# fpga-bank1.net
KiCad netlist of a schematic drawn in Altium Designer
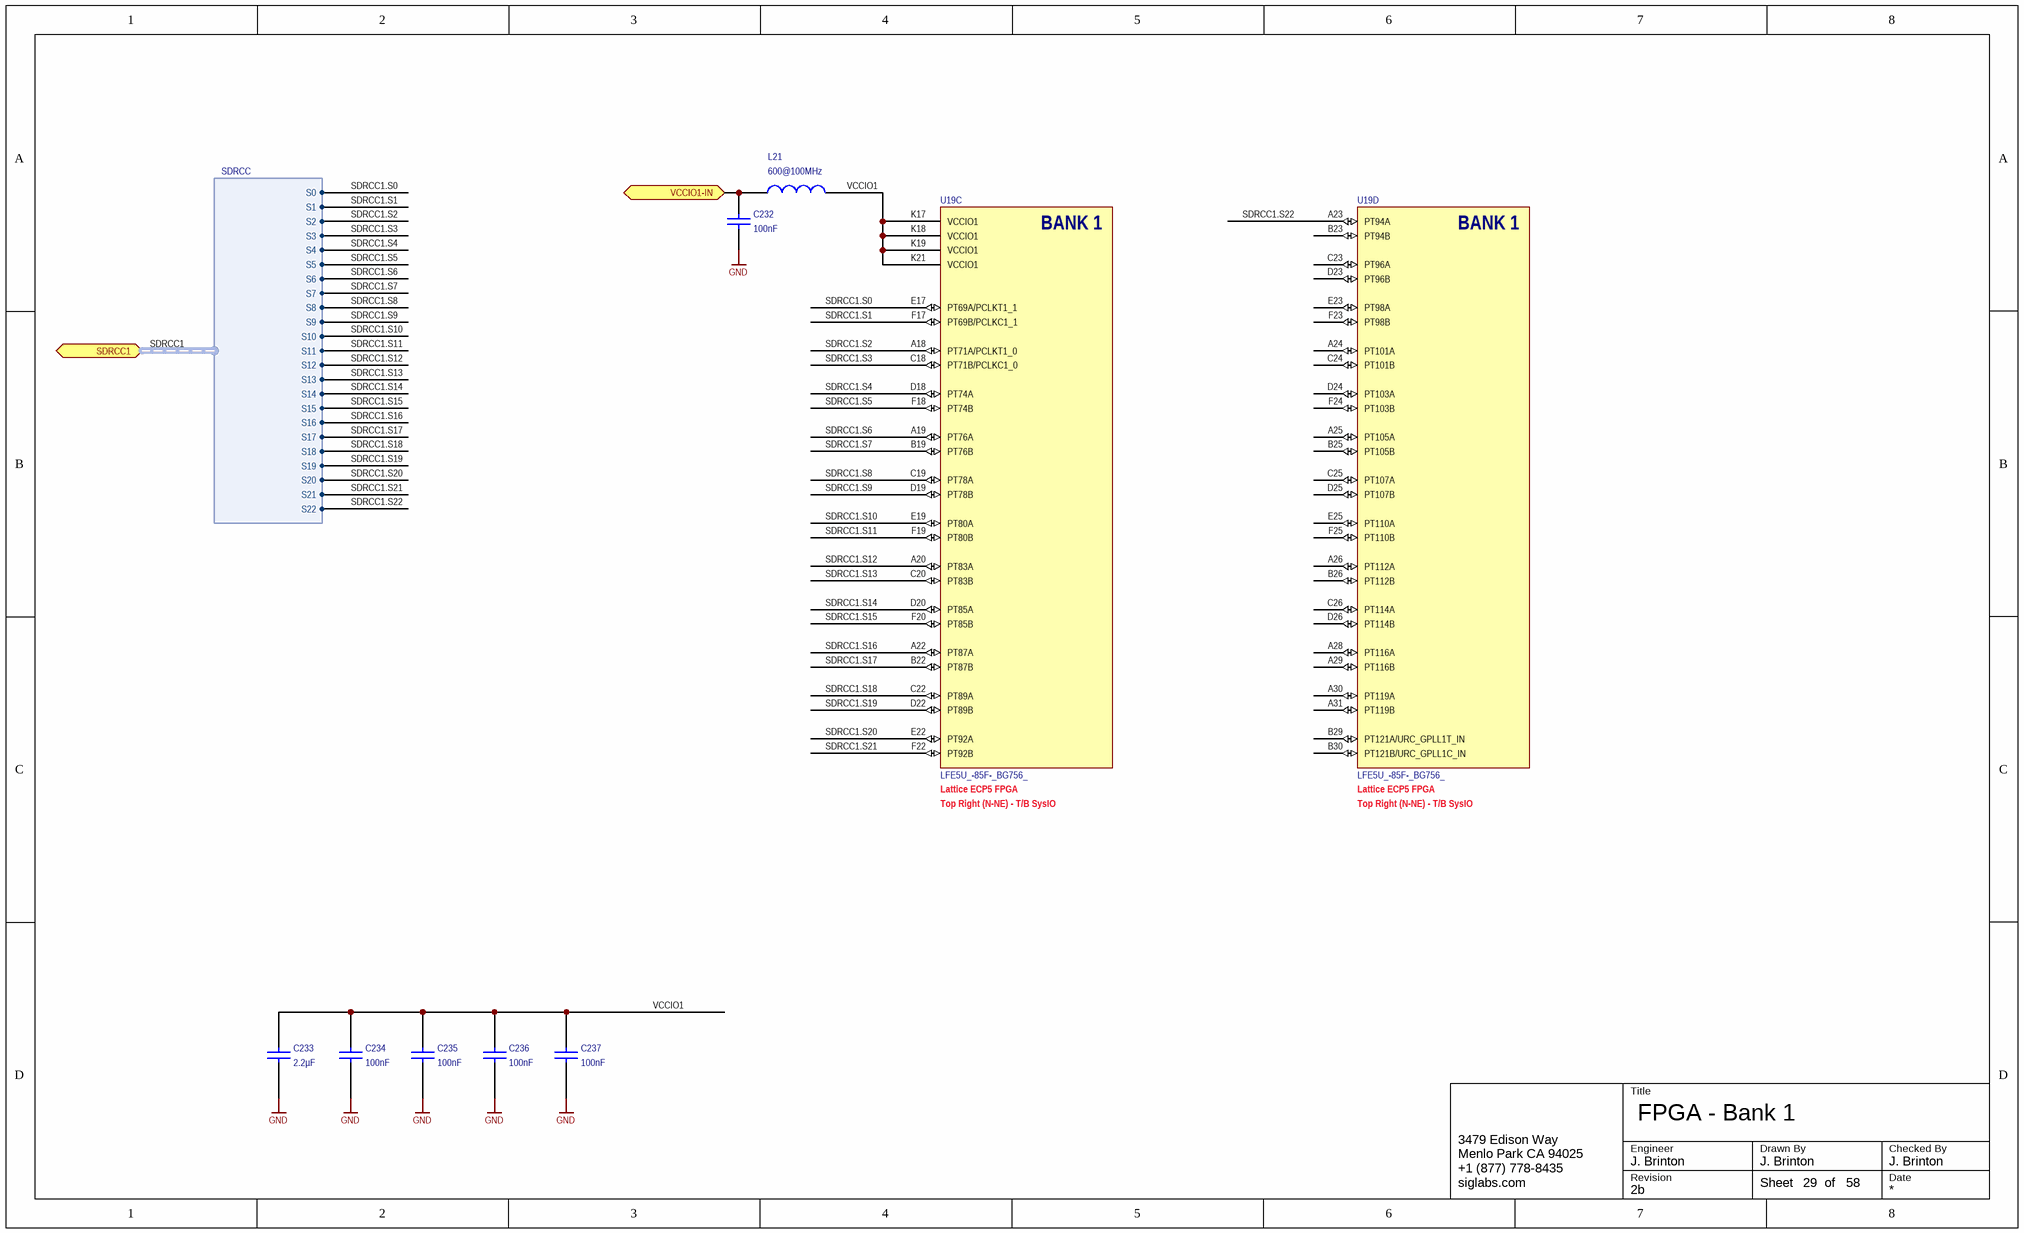
[diagram p0: fpga-bank1.SchDoc]

(export (version "E")
  (design (tool "Eeschema 10.0.6"))
  (components
    (comp (ref "C232")
      (value "100nF")
      (footprint "generic:CAPC1005X56N")
      (description "Ceramic Capacitor 100nF ±10% 16V X7R 0402")
      (fields (field (name "MANUFACTURER") "Murata") (field (name "TOLERANCE") "±10%"))
      (libsource (lib "murata") (part "GRM155R71A104KA01J"))
    )
    (comp (ref "C233")
      (value "2.2µF")
      (footprint "generic:CAPC1608X90N")
      (description "Ceramic Capacitor 2.2uF ±10% 10V X7R 0603")
      (fields (field (name "MANUFACTURER") "Murata") (field (name "TOLERANCE") "±10%"))
      (libsource (lib "murata") (part "GRM188R71A225KE15D"))
    )
    (comp (ref "C234")
      (value "100nF")
      (footprint "generic:CAPC1005X56N")
      (description "Ceramic Capacitor 100nF ±10% 16V X7R 0402")
      (fields (field (name "MANUFACTURER") "Murata") (field (name "TOLERANCE") "±10%"))
      (libsource (lib "murata") (part "GRM155R71A104KA01J"))
    )
    (comp (ref "C235")
      (value "100nF")
      (footprint "generic:CAPC1005X56N")
      (description "Ceramic Capacitor 100nF ±10% 16V X7R 0402")
      (fields (field (name "MANUFACTURER") "Murata") (field (name "TOLERANCE") "±10%"))
      (libsource (lib "murata") (part "GRM155R71A104KA01J"))
    )
    (comp (ref "C236")
      (value "100nF")
      (footprint "generic:CAPC1005X56N")
      (description "Ceramic Capacitor 100nF ±10% 16V X7R 0402")
      (fields (field (name "MANUFACTURER") "Murata") (field (name "TOLERANCE") "±10%"))
      (libsource (lib "murata") (part "GRM155R71A104KA01J"))
    )
    (comp (ref "C237")
      (value "100nF")
      (footprint "generic:CAPC1005X56N")
      (description "Ceramic Capacitor 100nF ±10% 16V X7R 0402")
      (fields (field (name "MANUFACTURER") "Murata") (field (name "TOLERANCE") "±10%"))
      (libsource (lib "murata") (part "GRM155R71A104KA01J"))
    )
    (comp (ref "L21")
      (value "600@100MHz")
      (footprint "0402")
      (description "Ferrite Bead 600-Ohm @ 100MHz 900mA 0402")
      (fields (field (name "MANUFACTURER") "Murata") (field (name "TOLERANCE") "±25%"))
      (libsource (lib "Graviton") (part "IND 0402"))
    )
    (comp (ref "U19")
      (value "LFE5U_-85F-_BG756_")
      (footprint "lattice:caBGA756")
      (description "ECP5 FPGA, 85k LUT, 756-caBGA")
      (fields (field (name "MANUFACTURER") "Lattice Semiconductor"))
      (libsource (lib "lattice") (part "LFE5U_-85F-_BG756_"))
    )
  )
  (nets
    (net (code "2") (name "/SDRCC1.S0") (class "Default")
      (node (ref "U19") (pin "E17") (pinfunction "PT69A/PCLKT1_1_E17") (pintype "bidirectional"))
    )
    (net (code "3") (name "/SDRCC1.S1") (class "Default")
      (node (ref "U19") (pin "F17") (pinfunction "PT69B/PCLKC1_1_F17") (pintype "bidirectional"))
    )
    (net (code "4") (name "/SDRCC1.S2") (class "Default")
      (node (ref "U19") (pin "A18") (pinfunction "PT71A/PCLKT1_0_A18") (pintype "bidirectional"))
    )
    (net (code "5") (name "/SDRCC1.S3") (class "Default")
      (node (ref "U19") (pin "C18") (pinfunction "PT71B/PCLKC1_0_C18") (pintype "bidirectional"))
    )
    (net (code "6") (name "/SDRCC1.S4") (class "Default")
      (node (ref "U19") (pin "D18") (pinfunction "PT74A_D18") (pintype "bidirectional"))
    )
    (net (code "7") (name "/SDRCC1.S5") (class "Default")
      (node (ref "U19") (pin "F18") (pinfunction "PT74B_F18") (pintype "bidirectional"))
    )
    (net (code "8") (name "/SDRCC1.S6") (class "Default")
      (node (ref "U19") (pin "A19") (pinfunction "PT76A_A19") (pintype "bidirectional"))
    )
    (net (code "9") (name "/SDRCC1.S7") (class "Default")
      (node (ref "U19") (pin "B19") (pinfunction "PT76B_B19") (pintype "bidirectional"))
    )
    (net (code "10") (name "/SDRCC1.S8") (class "Default")
      (node (ref "U19") (pin "C19") (pinfunction "PT78A_C19") (pintype "bidirectional"))
    )
    (net (code "11") (name "/SDRCC1.S9") (class "Default")
      (node (ref "U19") (pin "D19") (pinfunction "PT78B_D19") (pintype "bidirectional"))
    )
    (net (code "12") (name "/SDRCC1.S10") (class "Default")
      (node (ref "U19") (pin "E19") (pinfunction "PT80A_E19") (pintype "bidirectional"))
    )
    (net (code "13") (name "/SDRCC1.S11") (class "Default")
      (node (ref "U19") (pin "F19") (pinfunction "PT80B_F19") (pintype "bidirectional"))
    )
    (net (code "14") (name "/SDRCC1.S12") (class "Default")
      (node (ref "U19") (pin "A20") (pinfunction "PT83A_A20") (pintype "bidirectional"))
    )
    (net (code "15") (name "/SDRCC1.S13") (class "Default")
      (node (ref "U19") (pin "C20") (pinfunction "PT83B_C20") (pintype "bidirectional"))
    )
    (net (code "16") (name "/SDRCC1.S14") (class "Default")
      (node (ref "U19") (pin "D20") (pinfunction "PT85A_D20") (pintype "bidirectional"))
    )
    (net (code "17") (name "/SDRCC1.S15") (class "Default")
      (node (ref "U19") (pin "F20") (pinfunction "PT85B_F20") (pintype "bidirectional"))
    )
    (net (code "18") (name "/SDRCC1.S16") (class "Default")
      (node (ref "U19") (pin "A22") (pinfunction "PT87A_A22") (pintype "bidirectional"))
    )
    (net (code "19") (name "/SDRCC1.S17") (class "Default")
      (node (ref "U19") (pin "B22") (pinfunction "PT87B_B22") (pintype "bidirectional"))
    )
    (net (code "20") (name "/SDRCC1.S18") (class "Default")
      (node (ref "U19") (pin "C22") (pinfunction "PT89A_C22") (pintype "bidirectional"))
    )
    (net (code "21") (name "/SDRCC1.S19") (class "Default")
      (node (ref "U19") (pin "D22") (pinfunction "PT89B_D22") (pintype "bidirectional"))
    )
    (net (code "22") (name "/SDRCC1.S20") (class "Default")
      (node (ref "U19") (pin "E22") (pinfunction "PT92A_E22") (pintype "bidirectional"))
    )
    (net (code "23") (name "/SDRCC1.S21") (class "Default")
      (node (ref "U19") (pin "F22") (pinfunction "PT92B_F22") (pintype "bidirectional"))
    )
    (net (code "24") (name "/SDRCC1.S22") (class "Default")
      (node (ref "U19") (pin "A23") (pinfunction "PT94A_A23") (pintype "bidirectional"))
    )
    (net (code "26") (name "/VCCIO1") (class "Default")
      (node (ref "C233") (pin "2") (pinfunction "2_2") (pintype "passive"))
      (node (ref "C234") (pin "2") (pinfunction "2_2") (pintype "passive"))
      (node (ref "C235") (pin "2") (pinfunction "2_2") (pintype "passive"))
      (node (ref "C236") (pin "2") (pinfunction "2_2") (pintype "passive"))
      (node (ref "C237") (pin "2") (pinfunction "2_2") (pintype "passive"))
      (node (ref "L21") (pin "1") (pinfunction "1_1") (pintype "passive"))
      (node (ref "U19") (pin "K17") (pinfunction "VCCIO1_K17") (pintype "power_in"))
      (node (ref "U19") (pin "K18") (pinfunction "VCCIO1_K18") (pintype "power_in"))
      (node (ref "U19") (pin "K19") (pinfunction "VCCIO1_K19") (pintype "power_in"))
      (node (ref "U19") (pin "K21") (pinfunction "VCCIO1_K21") (pintype "power_in"))
    )
    (net (code "27") (name "/VCCIO1-IN") (class "Default")
      (node (ref "C232") (pin "2") (pinfunction "2_2") (pintype "passive"))
      (node (ref "L21") (pin "2") (pinfunction "2_2") (pintype "passive"))
    )
    (net (code "28") (name "GND") (class "Default")
      (node (ref "C232") (pin "1") (pinfunction "1_1") (pintype "passive"))
      (node (ref "C233") (pin "1") (pinfunction "1_1") (pintype "passive"))
      (node (ref "C234") (pin "1") (pinfunction "1_1") (pintype "passive"))
      (node (ref "C235") (pin "1") (pinfunction "1_1") (pintype "passive"))
      (node (ref "C236") (pin "1") (pinfunction "1_1") (pintype "passive"))
      (node (ref "C237") (pin "1") (pinfunction "1_1") (pintype "passive"))
    )
    (net (code "29") (name "unconnected-(U19D-PT94B-PadB23)") (class "Default")
      (node (ref "U19") (pin "B23") (pinfunction "PT94B_B23") (pintype "bidirectional"))
    )
    (net (code "30") (name "unconnected-(U19D-PT96A-PadC23)") (class "Default")
      (node (ref "U19") (pin "C23") (pinfunction "PT96A_C23") (pintype "bidirectional"))
    )
    (net (code "31") (name "unconnected-(U19D-PT96B-PadD23)") (class "Default")
      (node (ref "U19") (pin "D23") (pinfunction "PT96B_D23") (pintype "bidirectional"))
    )
    (net (code "32") (name "unconnected-(U19D-PT98A-PadE23)") (class "Default")
      (node (ref "U19") (pin "E23") (pinfunction "PT98A_E23") (pintype "bidirectional"))
    )
    (net (code "33") (name "unconnected-(U19D-PT98B-PadF23)") (class "Default")
      (node (ref "U19") (pin "F23") (pinfunction "PT98B_F23") (pintype "bidirectional"))
    )
    (net (code "34") (name "unconnected-(U19D-PT101A-PadA24)") (class "Default")
      (node (ref "U19") (pin "A24") (pinfunction "PT101A_A24") (pintype "bidirectional"))
    )
    (net (code "35") (name "unconnected-(U19D-PT101B-PadC24)") (class "Default")
      (node (ref "U19") (pin "C24") (pinfunction "PT101B_C24") (pintype "bidirectional"))
    )
    (net (code "36") (name "unconnected-(U19D-PT103A-PadD24)") (class "Default")
      (node (ref "U19") (pin "D24") (pinfunction "PT103A_D24") (pintype "bidirectional"))
    )
    (net (code "37") (name "unconnected-(U19D-PT103B-PadF24)") (class "Default")
      (node (ref "U19") (pin "F24") (pinfunction "PT103B_F24") (pintype "bidirectional"))
    )
    (net (code "38") (name "unconnected-(U19D-PT105A-PadA25)") (class "Default")
      (node (ref "U19") (pin "A25") (pinfunction "PT105A_A25") (pintype "bidirectional"))
    )
    (net (code "39") (name "unconnected-(U19D-PT105B-PadB25)") (class "Default")
      (node (ref "U19") (pin "B25") (pinfunction "PT105B_B25") (pintype "bidirectional"))
    )
    (net (code "40") (name "unconnected-(U19D-PT107A-PadC25)") (class "Default")
      (node (ref "U19") (pin "C25") (pinfunction "PT107A_C25") (pintype "bidirectional"))
    )
    (net (code "41") (name "unconnected-(U19D-PT107B-PadD25)") (class "Default")
      (node (ref "U19") (pin "D25") (pinfunction "PT107B_D25") (pintype "bidirectional"))
    )
    (net (code "42") (name "unconnected-(U19D-PT110A-PadE25)") (class "Default")
      (node (ref "U19") (pin "E25") (pinfunction "PT110A_E25") (pintype "bidirectional"))
    )
    (net (code "43") (name "unconnected-(U19D-PT110B-PadF25)") (class "Default")
      (node (ref "U19") (pin "F25") (pinfunction "PT110B_F25") (pintype "bidirectional"))
    )
    (net (code "44") (name "unconnected-(U19D-PT112A-PadA26)") (class "Default")
      (node (ref "U19") (pin "A26") (pinfunction "PT112A_A26") (pintype "bidirectional"))
    )
    (net (code "45") (name "unconnected-(U19D-PT112B-PadB26)") (class "Default")
      (node (ref "U19") (pin "B26") (pinfunction "PT112B_B26") (pintype "bidirectional"))
    )
    (net (code "46") (name "unconnected-(U19D-PT114A-PadC26)") (class "Default")
      (node (ref "U19") (pin "C26") (pinfunction "PT114A_C26") (pintype "bidirectional"))
    )
    (net (code "47") (name "unconnected-(U19D-PT114B-PadD26)") (class "Default")
      (node (ref "U19") (pin "D26") (pinfunction "PT114B_D26") (pintype "bidirectional"))
    )
    (net (code "48") (name "unconnected-(U19D-PT116A-PadA28)") (class "Default")
      (node (ref "U19") (pin "A28") (pinfunction "PT116A_A28") (pintype "bidirectional"))
    )
    (net (code "49") (name "unconnected-(U19D-PT116B-PadA29)") (class "Default")
      (node (ref "U19") (pin "A29") (pinfunction "PT116B_A29") (pintype "bidirectional"))
    )
    (net (code "50") (name "unconnected-(U19D-PT119A-PadA30)") (class "Default")
      (node (ref "U19") (pin "A30") (pinfunction "PT119A_A30") (pintype "bidirectional"))
    )
    (net (code "51") (name "unconnected-(U19D-PT119B-PadA31)") (class "Default")
      (node (ref "U19") (pin "A31") (pinfunction "PT119B_A31") (pintype "bidirectional"))
    )
    (net (code "52") (name "unconnected-(U19D-PT121A{slash}URC_GPLL1T_IN-PadB29)") (class "Default")
      (node (ref "U19") (pin "B29") (pinfunction "PT121A/URC_GPLL1T_IN_B29") (pintype "bidirectional"))
    )
    (net (code "53") (name "unconnected-(U19D-PT121B{slash}URC_GPLL1C_IN-PadB30)") (class "Default")
      (node (ref "U19") (pin "B30") (pinfunction "PT121B/URC_GPLL1C_IN_B30") (pintype "bidirectional"))
    )
  )
)
